# wio_shield_v2.net
KiCad netlist of a schematic drawn in EAGLE
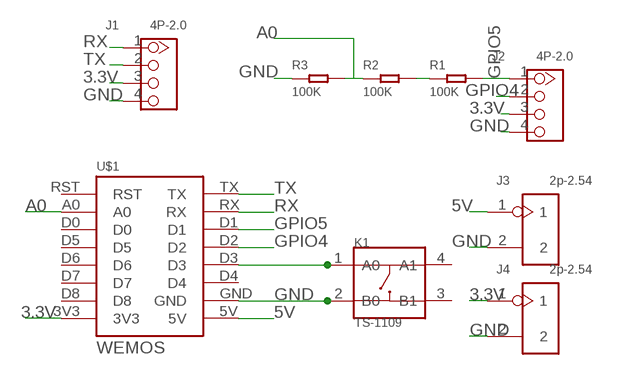
[diagram p0: schematic, sheet 1]

(export (version "E")
  (design (tool "Eeschema 10.0.6"))
  (components
    (comp (ref "J1")
      (value "4P-2.0")
      (footprint "eagle-import:HW4-2.0")
      (libsource (lib "eagle-import") (part "GROVE-CONNECTOR-DIP(4P-2.0)"))
    )
    (comp (ref "J2")
      (value "4P-2.0")
      (footprint "eagle-import:HW4-2.0")
      (libsource (lib "eagle-import") (part "GROVE-CONNECTOR-DIP(4P-2.0)"))
    )
    (comp (ref "J3")
      (value "2p-2.54")
      (footprint "eagle-import:H2-2.54")
      (fields (field (name "MPN") "P125-1102A0BS116A2"))
      (libsource (lib "eagle-import") (part "DIP-BLUE-MALE-HEADER-VERT(2P-2.54)"))
    )
    (comp (ref "J4")
      (value "2p-2.54")
      (footprint "eagle-import:H2-2.54")
      (fields (field (name "MPN") "P125-1102A0BS116A2"))
      (libsource (lib "eagle-import") (part "DIP-BLUE-MALE-HEADER-VERT(2P-2.54)"))
    )
    (comp (ref "K1")
      (value "TS-1109")
      (footprint "eagle-import:SW4-6.0X6.0X5.0MM")
      (libsource (lib "eagle-import") (part "DIP-BUTTON-4P"))
    )
    (comp (ref "R1")
      (value "100K")
      (footprint "eagle-import:PR-D1.8_L3.3MM")
      (fields (field (name "MPN") "FHCFR-1/6W-104J--"))
      (libsource (lib "eagle-import") (part "DIP-RES-100K-5%-1/6W(PR-D1.8XL3.3MM)"))
    )
    (comp (ref "R2")
      (value "100K")
      (footprint "eagle-import:PR-D1.8_L3.3MM")
      (fields (field (name "MPN") "FHCFR-1/6W-104J--"))
      (libsource (lib "eagle-import") (part "DIP-RES-100K-5%-1/6W(PR-D1.8XL3.3MM)"))
    )
    (comp (ref "R3")
      (value "100K")
      (footprint "eagle-import:PR-D1.8_L3.3MM")
      (fields (field (name "MPN") "FHCFR-1/6W-104J--"))
      (libsource (lib "eagle-import") (part "DIP-RES-100K-5%-1/6W(PR-D1.8XL3.3MM)"))
    )
    (comp (ref "U$1")
      (value "WEMOS")
      (footprint "eagle-import:WEMOS")
      (libsource (lib "eagle-import") (part "WEMOS"))
    )
  )
  (nets
    (net (code "1") (name "/3.3V") (class "Default")
      (node (ref "J1") (pin "3") (pinfunction "3_3") (pintype "bidirectional"))
      (node (ref "J2") (pin "3") (pinfunction "3_3") (pintype "bidirectional"))
      (node (ref "J4") (pin "1") (pinfunction "1_1") (pintype "bidirectional"))
      (node (ref "U$1") (pin "3V3") (pinfunction "3V3_3V3") (pintype "bidirectional"))
    )
    (net (code "2") (name "/5V") (class "Default")
      (node (ref "J3") (pin "1") (pinfunction "1_1") (pintype "bidirectional"))
      (node (ref "U$1") (pin "5V") (pinfunction "5V_5V") (pintype "bidirectional"))
    )
    (net (code "3") (name "/A0") (class "Default")
      (node (ref "R2") (pin "6") (pinfunction "1_6") (pintype "passive"))
      (node (ref "R3") (pin "5") (pinfunction "2_5") (pintype "passive"))
      (node (ref "U$1") (pin "A0") (pinfunction "A0_A0") (pintype "bidirectional"))
    )
    (net (code "4") (name "/GND") (class "Default")
      (node (ref "J1") (pin "4") (pinfunction "4_4") (pintype "bidirectional"))
      (node (ref "J2") (pin "4") (pinfunction "4_4") (pintype "bidirectional"))
      (node (ref "J3") (pin "2") (pinfunction "2_2") (pintype "bidirectional"))
      (node (ref "J4") (pin "2") (pinfunction "2_2") (pintype "bidirectional"))
      (node (ref "K1") (pin "2") (pinfunction "B0_2") (pintype "bidirectional"))
      (node (ref "R3") (pin "6") (pinfunction "1_6") (pintype "passive"))
      (node (ref "U$1") (pin "GND") (pinfunction "GND_GND") (pintype "bidirectional"))
    )
    (net (code "5") (name "/GPIO4") (class "Default")
      (node (ref "J2") (pin "2") (pinfunction "2_2") (pintype "bidirectional"))
      (node (ref "U$1") (pin "D2") (pinfunction "D2_D2") (pintype "bidirectional"))
    )
    (net (code "6") (name "/GPIO5") (class "Default")
      (node (ref "J2") (pin "1") (pinfunction "1_1") (pintype "bidirectional"))
      (node (ref "R1") (pin "5") (pinfunction "2_5") (pintype "passive"))
      (node (ref "U$1") (pin "D1") (pinfunction "D1_D1") (pintype "bidirectional"))
    )
    (net (code "7") (name "/RX") (class "Default")
      (node (ref "J1") (pin "1") (pinfunction "1_1") (pintype "bidirectional"))
      (node (ref "U$1") (pin "RX") (pinfunction "RX_RX") (pintype "bidirectional"))
    )
    (net (code "8") (name "/TX") (class "Default")
      (node (ref "J1") (pin "2") (pinfunction "2_2") (pintype "bidirectional"))
      (node (ref "U$1") (pin "TX") (pinfunction "TX_TX") (pintype "bidirectional"))
    )
    (net (code "9") (name "Net-(K1-A0)") (class "Default")
      (node (ref "K1") (pin "1") (pinfunction "A0_1") (pintype "bidirectional"))
      (node (ref "U$1") (pin "D3") (pinfunction "D3_D3") (pintype "bidirectional"))
    )
    (net (code "10") (name "Net-(R1-1)") (class "Default")
      (node (ref "R1") (pin "6") (pinfunction "1_6") (pintype "passive"))
      (node (ref "R2") (pin "5") (pinfunction "2_5") (pintype "passive"))
    )
    (net (code "11") (name "unconnected-(K1-A1-Pad4)") (class "Default")
      (node (ref "K1") (pin "4") (pinfunction "A1_4") (pintype "bidirectional"))
    )
    (net (code "12") (name "unconnected-(K1-B1-Pad3)") (class "Default")
      (node (ref "K1") (pin "3") (pinfunction "B1_3") (pintype "bidirectional"))
    )
    (net (code "13") (name "unconnected-(U$1-PadD0)") (class "Default")
      (node (ref "U$1") (pin "D0") (pinfunction "D0_D0") (pintype "bidirectional"))
    )
    (net (code "14") (name "unconnected-(U$1-PadD4)") (class "Default")
      (node (ref "U$1") (pin "D4") (pinfunction "D4_D4") (pintype "bidirectional"))
    )
    (net (code "15") (name "unconnected-(U$1-PadD5)") (class "Default")
      (node (ref "U$1") (pin "D5") (pinfunction "D5_D5") (pintype "bidirectional"))
    )
    (net (code "16") (name "unconnected-(U$1-PadD6)") (class "Default")
      (node (ref "U$1") (pin "D6") (pinfunction "D6_D6") (pintype "bidirectional"))
    )
    (net (code "17") (name "unconnected-(U$1-PadD7)") (class "Default")
      (node (ref "U$1") (pin "D7") (pinfunction "D7_D7") (pintype "bidirectional"))
    )
    (net (code "18") (name "unconnected-(U$1-PadD8)") (class "Default")
      (node (ref "U$1") (pin "D8") (pinfunction "D8_D8") (pintype "bidirectional"))
    )
    (net (code "19") (name "unconnected-(U$1-PadRST)") (class "Default")
      (node (ref "U$1") (pin "RST") (pinfunction "RST_RST") (pintype "bidirectional"))
    )
  )
)
